# ESCV3.net
KiCad netlist of a schematic drawn in Altium Designer
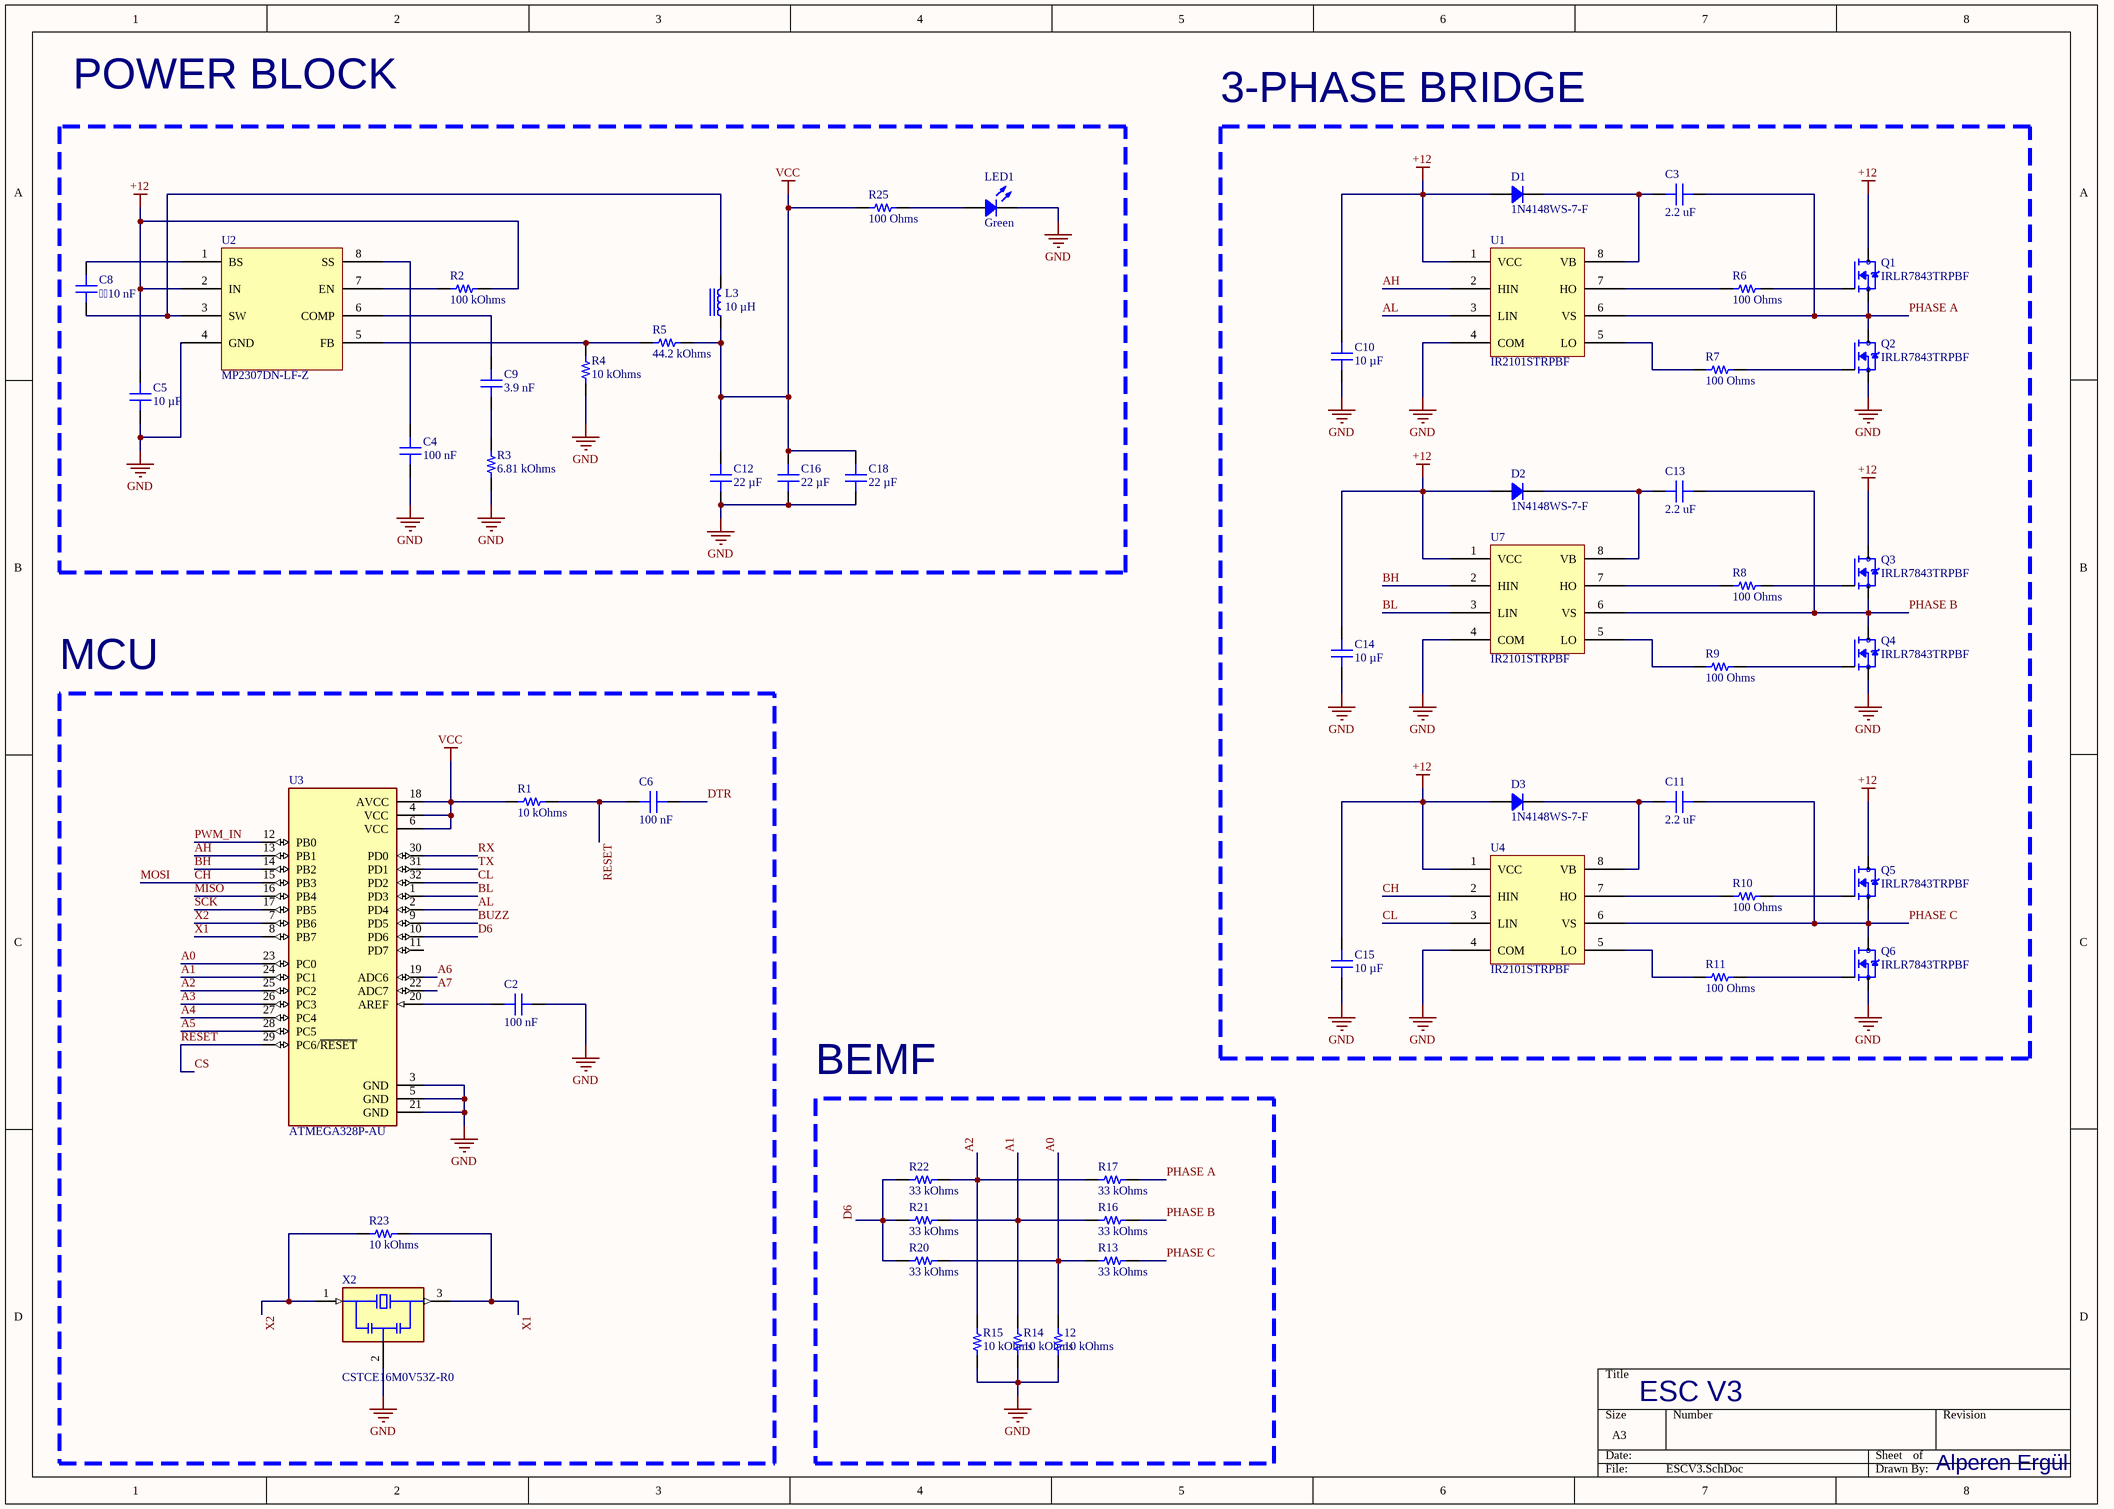
[diagram p0: ESCV3.SchDoc]

(export (version "E")
  (design (tool "Eeschema 10.0.6"))
  (components
    (comp (ref "12")
      (value "10 kOhms")
      (footprint "RES 0603_1608")
      (description "RES 10K OHM 0.1% 1/16W 0603")
      (fields
        (field (name "PART NUMBER") "RNCS0603BKE10K0")
        (field (name "MANUFACTURER") "Stackpole Electronics Inc")
      )
      (libsource (lib "Celestial Altium Library - altium_library") (part "Resistor"))
    )
    (comp (ref "C2")
      (value "100 nF")
      (footprint "CAP 0603_1608")
      (description "CAP CER 3.9PF 250V C0G/NP0 0603")
      (fields (field (name "PART NUMBER") "CBR06C399BAGAC") (field (name "MANUFACTURER") "KEMET"))
      (libsource (lib "Celestial Altium Library - altium_library") (part "Capacitor"))
    )
    (comp (ref "C3")
      (value "2.2 uF")
      (footprint "CAP 0603_1608")
      (description "CAP CER 3.9PF 250V C0G/NP0 0603")
      (fields (field (name "PART NUMBER") "CBR06C399BAGAC") (field (name "MANUFACTURER") "KEMET"))
      (libsource (lib "Celestial Altium Library - altium_library") (part "Capacitor"))
    )
    (comp (ref "C4")
      (value "100 nF")
      (footprint "CAP 0603_1608")
      (description "CAP CER 3.9PF 250V C0G/NP0 0603")
      (fields (field (name "PART NUMBER") "CBR06C399BAGAC") (field (name "MANUFACTURER") "KEMET"))
      (libsource (lib "Celestial Altium Library - altium_library") (part "Capacitor"))
    )
    (comp (ref "C5")
      (value "10 µF")
      (footprint "CAP 1206_3216 - 0.8MM")
      (description "CAP CER 10UF 16V X5R 1206")
      (fields (field (name "PART NUMBER") "EMK316BJ106MD-T") (field (name "MANUFACTURER") "Taiyo Yuden"))
      (libsource (lib "Celestial Altium Library - altium_library") (part "Capacitor"))
    )
    (comp (ref "C6")
      (value "100 nF")
      (footprint "CAP 0603_1608")
      (description "CAP CER 3.9PF 250V C0G/NP0 0603")
      (fields (field (name "PART NUMBER") "CBR06C399BAGAC") (field (name "MANUFACTURER") "KEMET"))
      (libsource (lib "Celestial Altium Library - altium_library") (part "Capacitor"))
    )
    (comp (ref "C8")
      (value "10 nF")
      (footprint "CAP 0603_1608")
      (description "CAP CER 3.9PF 250V C0G/NP0 0603")
      (fields (field (name "PART NUMBER") "CBR06C399BAGAC") (field (name "MANUFACTURER") "KEMET"))
      (libsource (lib "Celestial Altium Library - altium_library") (part "Capacitor"))
    )
    (comp (ref "C9")
      (value "3.9 nF")
      (footprint "CAP 0603_1608")
      (description "CAP CER 3.9PF 250V C0G/NP0 0603")
      (fields (field (name "PART NUMBER") "CBR06C399BAGAC") (field (name "MANUFACTURER") "KEMET"))
      (libsource (lib "Celestial Altium Library - altium_library") (part "Capacitor"))
    )
    (comp (ref "C10")
      (value "10 µF")
      (footprint "CAP 1206_3216 - 0.8MM")
      (description "CAP CER 10UF 16V X5R 1206")
      (fields (field (name "PART NUMBER") "EMK316BJ106MD-T") (field (name "MANUFACTURER") "Taiyo Yuden"))
      (libsource (lib "Celestial Altium Library - altium_library") (part "Capacitor"))
    )
    (comp (ref "C11")
      (value "2.2 uF")
      (footprint "CAP 0603_1608")
      (description "CAP CER 3.9PF 250V C0G/NP0 0603")
      (fields (field (name "PART NUMBER") "CBR06C399BAGAC") (field (name "MANUFACTURER") "KEMET"))
      (libsource (lib "Celestial Altium Library - altium_library") (part "Capacitor"))
    )
    (comp (ref "C12")
      (value "22 µF")
      (footprint "CAP 1206_3216 - 0.8MM")
      (description "CAP CER 22UF 16V X5R 1206")
      (fields
        (field (name "PART NUMBER") "CL31A226MOCLNNC")
        (field (name "MANUFACTURER") "Samsung Electro-Mechanics")
      )
      (libsource (lib "Celestial Altium Library - altium_library") (part "Capacitor"))
    )
    (comp (ref "C13")
      (value "2.2 uF")
      (footprint "CAP 0603_1608")
      (description "CAP CER 3.9PF 250V C0G/NP0 0603")
      (fields (field (name "PART NUMBER") "CBR06C399BAGAC") (field (name "MANUFACTURER") "KEMET"))
      (libsource (lib "Celestial Altium Library - altium_library") (part "Capacitor"))
    )
    (comp (ref "C14")
      (value "10 µF")
      (footprint "CAP 1206_3216 - 0.8MM")
      (description "CAP CER 10UF 16V X5R 1206")
      (fields (field (name "PART NUMBER") "EMK316BJ106MD-T") (field (name "MANUFACTURER") "Taiyo Yuden"))
      (libsource (lib "Celestial Altium Library - altium_library") (part "Capacitor"))
    )
    (comp (ref "C15")
      (value "10 µF")
      (footprint "CAP 1206_3216 - 0.8MM")
      (description "CAP CER 10UF 16V X5R 1206")
      (fields (field (name "PART NUMBER") "EMK316BJ106MD-T") (field (name "MANUFACTURER") "Taiyo Yuden"))
      (libsource (lib "Celestial Altium Library - altium_library") (part "Capacitor"))
    )
    (comp (ref "C16")
      (value "22 µF")
      (footprint "CAP 1206_3216 - 0.8MM")
      (description "CAP CER 22UF 16V X5R 1206")
      (fields
        (field (name "PART NUMBER") "CL31A226MOCLNNC")
        (field (name "MANUFACTURER") "Samsung Electro-Mechanics")
      )
      (libsource (lib "Celestial Altium Library - altium_library") (part "Capacitor"))
    )
    (comp (ref "C18")
      (value "22 µF")
      (footprint "CAP 1206_3216 - 0.8MM")
      (description "CAP CER 22UF 16V X5R 1206")
      (fields
        (field (name "PART NUMBER") "CL31A226MOCLNNC")
        (field (name "MANUFACTURER") "Samsung Electro-Mechanics")
      )
      (libsource (lib "Celestial Altium Library - altium_library") (part "Capacitor"))
    )
    (comp (ref "D1")
      (value "1N4148WS-7-F")
      (footprint "SOD323")
      (description "DIODE GEN PURP 75V 150MA SOD323")
      (fields (field (name "MANUFACTURER") "Diodes Incorporated"))
      (libsource (lib "Celestial Altium Library - altium_library") (part "Diode"))
    )
    (comp (ref "D2")
      (value "1N4148WS-7-F")
      (footprint "SOD323")
      (description "DIODE GEN PURP 75V 150MA SOD323")
      (fields (field (name "MANUFACTURER") "Diodes Incorporated"))
      (libsource (lib "Celestial Altium Library - altium_library") (part "Diode"))
    )
    (comp (ref "D3")
      (value "1N4148WS-7-F")
      (footprint "SOD323")
      (description "DIODE GEN PURP 75V 150MA SOD323")
      (fields (field (name "MANUFACTURER") "Diodes Incorporated"))
      (libsource (lib "Celestial Altium Library - altium_library") (part "Diode"))
    )
    (comp (ref "L3")
      (value "10 µH")
      (footprint "BOURNS SRP5030T")
      (description "FIXED IND 10UH 2.75A 128MOHM SMD")
      (fields (field (name "PART NUMBER") "SRP5030T-100M") (field (name "MANUFACTURER") "Bourns Inc."))
      (libsource (lib "Celestial Altium Library - altium_library") (part "Inductor"))
    )
    (comp (ref "LED1")
      (value "Green")
      (footprint "LED 0603_1608 GREEN")
      (description "LED GREEN CLEAR CHIP 0603 SMD")
      (fields
        (field (name "PART NUMBER") "LSM0603453V")
        (field (name "MANUFACTURER") "Visual Communications Company - VCC")
      )
      (libsource (lib "Celestial Altium Library - altium_library") (part "LED"))
    )
    (comp (ref "Q1")
      (value "IRLR7843TRPBF")
      (footprint "TO229P990X239-3_4N")
      (fields (field (name "MF") "Infineon Technologies"))
      (libsource (lib "IRLR7843TRPBF") (part "IRLR7843TRPBF"))
    )
    (comp (ref "Q2")
      (value "IRLR7843TRPBF")
      (footprint "TO229P990X239-3_4N")
      (fields (field (name "MF") "Infineon Technologies"))
      (libsource (lib "IRLR7843TRPBF") (part "IRLR7843TRPBF"))
    )
    (comp (ref "Q3")
      (value "IRLR7843TRPBF")
      (footprint "TO229P990X239-3_4N")
      (fields (field (name "MF") "Infineon Technologies"))
      (libsource (lib "IRLR7843TRPBF") (part "IRLR7843TRPBF"))
    )
    (comp (ref "Q4")
      (value "IRLR7843TRPBF")
      (footprint "TO229P990X239-3_4N")
      (fields (field (name "MF") "Infineon Technologies"))
      (libsource (lib "IRLR7843TRPBF") (part "IRLR7843TRPBF"))
    )
    (comp (ref "Q5")
      (value "IRLR7843TRPBF")
      (footprint "TO229P990X239-3_4N")
      (fields (field (name "MF") "Infineon Technologies"))
      (libsource (lib "IRLR7843TRPBF") (part "IRLR7843TRPBF"))
    )
    (comp (ref "Q6")
      (value "IRLR7843TRPBF")
      (footprint "TO229P990X239-3_4N")
      (fields (field (name "MF") "Infineon Technologies"))
      (libsource (lib "IRLR7843TRPBF") (part "IRLR7843TRPBF"))
    )
    (comp (ref "R1")
      (value "10 kOhms")
      (footprint "RES 0603_1608")
      (description "RES 10K OHM 0.1% 1/16W 0603")
      (fields
        (field (name "PART NUMBER") "RNCS0603BKE10K0")
        (field (name "MANUFACTURER") "Stackpole Electronics Inc")
      )
      (libsource (lib "Celestial Altium Library - altium_library") (part "Resistor"))
    )
    (comp (ref "R2")
      (value "100 kOhms")
      (footprint "RES 0603_1608")
      (description "RES 100K OHM 0.1% 1/16W 0603")
      (fields
        (field (name "PART NUMBER") "RNCS0603BKE100K")
        (field (name "MANUFACTURER") "Stackpole Electronics Inc")
      )
      (libsource (lib "Celestial Altium Library - altium_library") (part "Resistor"))
    )
    (comp (ref "R3")
      (value "6.81 kOhms")
      (footprint "RES 0603_1608")
      (description "RQ 0603 6K81 0.1% 10PPM 1K RL")
      (fields
        (field (name "PART NUMBER") "RQ73C1J6K81BTDF")
        (field (name "MANUFACTURER") "TE Connectivity Passive Product")
      )
      (libsource (lib "Celestial Altium Library - altium_library") (part "Resistor"))
    )
    (comp (ref "R4")
      (value "10 kOhms")
      (footprint "RES 0603_1608")
      (description "RES 10K OHM 0.1% 1/16W 0603")
      (fields
        (field (name "PART NUMBER") "RNCS0603BKE10K0")
        (field (name "MANUFACTURER") "Stackpole Electronics Inc")
      )
      (libsource (lib "Celestial Altium Library - altium_library") (part "Resistor"))
    )
    (comp (ref "R5")
      (value "44.2 kOhms")
      (footprint "RES 0603_1608")
      (description "RES SMD 44.2K OHM 0.1% 1/5W 0603")
      (fields
        (field (name "PART NUMBER") "ERJ-PB3B4422V")
        (field (name "MANUFACTURER") "Panasonic Electronic Components")
      )
      (libsource (lib "Celestial Altium Library - altium_library") (part "Resistor"))
    )
    (comp (ref "R6")
      (value "100 Ohms")
      (footprint "RES 0603_1608")
      (description "RES 100 OHM 0.1% 1/16W 0603")
      (fields
        (field (name "PART NUMBER") "RNCS0603BKE100R")
        (field (name "MANUFACTURER") "Stackpole Electronics Inc")
      )
      (libsource (lib "Celestial Altium Library - altium_library") (part "Resistor"))
    )
    (comp (ref "R7")
      (value "100 Ohms")
      (footprint "RES 0603_1608")
      (description "RES 100 OHM 0.1% 1/16W 0603")
      (fields
        (field (name "PART NUMBER") "RNCS0603BKE100R")
        (field (name "MANUFACTURER") "Stackpole Electronics Inc")
      )
      (libsource (lib "Celestial Altium Library - altium_library") (part "Resistor"))
    )
    (comp (ref "R8")
      (value "100 Ohms")
      (footprint "RES 0603_1608")
      (description "RES 100 OHM 0.1% 1/16W 0603")
      (fields
        (field (name "PART NUMBER") "RNCS0603BKE100R")
        (field (name "MANUFACTURER") "Stackpole Electronics Inc")
      )
      (libsource (lib "Celestial Altium Library - altium_library") (part "Resistor"))
    )
    (comp (ref "R9")
      (value "100 Ohms")
      (footprint "RES 0603_1608")
      (description "RES 100 OHM 0.1% 1/16W 0603")
      (fields
        (field (name "PART NUMBER") "RNCS0603BKE100R")
        (field (name "MANUFACTURER") "Stackpole Electronics Inc")
      )
      (libsource (lib "Celestial Altium Library - altium_library") (part "Resistor"))
    )
    (comp (ref "R10")
      (value "100 Ohms")
      (footprint "RES 0603_1608")
      (description "RES 100 OHM 0.1% 1/16W 0603")
      (fields
        (field (name "PART NUMBER") "RNCS0603BKE100R")
        (field (name "MANUFACTURER") "Stackpole Electronics Inc")
      )
      (libsource (lib "Celestial Altium Library - altium_library") (part "Resistor"))
    )
    (comp (ref "R11")
      (value "100 Ohms")
      (footprint "RES 0603_1608")
      (description "RES 100 OHM 0.1% 1/16W 0603")
      (fields
        (field (name "PART NUMBER") "RNCS0603BKE100R")
        (field (name "MANUFACTURER") "Stackpole Electronics Inc")
      )
      (libsource (lib "Celestial Altium Library - altium_library") (part "Resistor"))
    )
    (comp (ref "R13")
      (value "33 kOhms")
      (footprint "RES 0603_1608")
      (description "RES SMD 33K OHM 0.1% 1/16W 0603")
      (fields
        (field (name "PART NUMBER") "CPF0603B33KE1")
        (field (name "MANUFACTURER") "TE Connectivity Passive Product")
      )
      (libsource (lib "Celestial Altium Library - altium_library") (part "Resistor"))
    )
    (comp (ref "R14")
      (value "10 kOhms")
      (footprint "RES 0603_1608")
      (description "RES 10K OHM 0.1% 1/16W 0603")
      (fields
        (field (name "PART NUMBER") "RNCS0603BKE10K0")
        (field (name "MANUFACTURER") "Stackpole Electronics Inc")
      )
      (libsource (lib "Celestial Altium Library - altium_library") (part "Resistor"))
    )
    (comp (ref "R15")
      (value "10 kOhms")
      (footprint "RES 0603_1608")
      (description "RES 10K OHM 0.1% 1/16W 0603")
      (fields
        (field (name "PART NUMBER") "RNCS0603BKE10K0")
        (field (name "MANUFACTURER") "Stackpole Electronics Inc")
      )
      (libsource (lib "Celestial Altium Library - altium_library") (part "Resistor"))
    )
    (comp (ref "R16")
      (value "33 kOhms")
      (footprint "RES 0603_1608")
      (description "RES SMD 33K OHM 0.1% 1/16W 0603")
      (fields
        (field (name "PART NUMBER") "CPF0603B33KE1")
        (field (name "MANUFACTURER") "TE Connectivity Passive Product")
      )
      (libsource (lib "Celestial Altium Library - altium_library") (part "Resistor"))
    )
    (comp (ref "R17")
      (value "33 kOhms")
      (footprint "RES 0603_1608")
      (description "RES SMD 33K OHM 0.1% 1/16W 0603")
      (fields
        (field (name "PART NUMBER") "CPF0603B33KE1")
        (field (name "MANUFACTURER") "TE Connectivity Passive Product")
      )
      (libsource (lib "Celestial Altium Library - altium_library") (part "Resistor"))
    )
    (comp (ref "R20")
      (value "33 kOhms")
      (footprint "RES 0603_1608")
      (description "RES SMD 33K OHM 0.1% 1/16W 0603")
      (fields
        (field (name "PART NUMBER") "CPF0603B33KE1")
        (field (name "MANUFACTURER") "TE Connectivity Passive Product")
      )
      (libsource (lib "Celestial Altium Library - altium_library") (part "Resistor"))
    )
    (comp (ref "R21")
      (value "33 kOhms")
      (footprint "RES 0603_1608")
      (description "RES SMD 33K OHM 0.1% 1/16W 0603")
      (fields
        (field (name "PART NUMBER") "CPF0603B33KE1")
        (field (name "MANUFACTURER") "TE Connectivity Passive Product")
      )
      (libsource (lib "Celestial Altium Library - altium_library") (part "Resistor"))
    )
    (comp (ref "R22")
      (value "33 kOhms")
      (footprint "RES 0603_1608")
      (description "RES SMD 33K OHM 0.1% 1/16W 0603")
      (fields
        (field (name "PART NUMBER") "CPF0603B33KE1")
        (field (name "MANUFACTURER") "TE Connectivity Passive Product")
      )
      (libsource (lib "Celestial Altium Library - altium_library") (part "Resistor"))
    )
    (comp (ref "R23")
      (value "10 kOhms")
      (footprint "RES 0603_1608")
      (description "RES 10K OHM 0.1% 1/16W 0603")
      (fields
        (field (name "PART NUMBER") "RNCS0603BKE10K0")
        (field (name "MANUFACTURER") "Stackpole Electronics Inc")
      )
      (libsource (lib "Celestial Altium Library - altium_library") (part "Resistor"))
    )
    (comp (ref "R25")
      (value "100 Ohms")
      (footprint "RES 0603_1608")
      (description "RES 100 OHM 0.1% 1/16W 0603")
      (fields
        (field (name "PART NUMBER") "RNCS0603BKE100R")
        (field (name "MANUFACTURER") "Stackpole Electronics Inc")
      )
      (libsource (lib "Celestial Altium Library - altium_library") (part "Resistor"))
    )
    (comp (ref "U1")
      (value "IR2101STRPBF")
      (footprint "IR2101STRPBF")
      (libsource (lib "ESCV3") (part "IR2101STRPBF"))
    )
    (comp (ref "U2")
      (value "MP2307DN-LF-Z")
      (footprint "MP2307DN-LF-Z")
      (libsource (lib "ESCV3") (part "MP2307DN-LF-Z"))
    )
    (comp (ref "U3")
      (value "ATMEGA328P-AU")
      (footprint "QFP80P900X900X120-32N")
      (description "AVR AVRÂ® ATmega Microcontroller IC 8-Bit 20MHz 32KB (16K x 16) FLASH 32-TQFP (7x7)")
      (fields (field (name "MF") "Microchip Technology"))
      (libsource (lib "ATMEGA328P-AU") (part "ATMEGA328P-AU"))
    )
    (comp (ref "U4")
      (value "IR2101STRPBF")
      (footprint "IR2101STRPBF")
      (libsource (lib "ESCV3") (part "IR2101STRPBF"))
    )
    (comp (ref "U7")
      (value "IR2101STRPBF")
      (footprint "IR2101STRPBF")
      (libsource (lib "ESCV3") (part "IR2101STRPBF"))
    )
    (comp (ref "X2")
      (value "CSTCE16M0V53Z-R0")
      (footprint "OSC_CSTCE16M0V53Z-R0")
      (description "20MHz Ceramic Resonator Built in Capacitor 15pF +/- 0.2% -40C - 125C Surface Mount")
      (fields (field (name "MF") "Murata"))
      (libsource (lib "CSTCE16M0V53Z-R0") (part "CSTCE16M0V53Z-R0"))
    )
  )
  (nets
    (net (code "1") (name "+12") (class "Default")
      (node (ref "C10") (pin "2") (pinfunction "2_2") (pintype "passive"))
      (node (ref "C14") (pin "2") (pinfunction "2_2") (pintype "passive"))
      (node (ref "C15") (pin "2") (pinfunction "2_2") (pintype "passive"))
      (node (ref "C5") (pin "2") (pinfunction "2_2") (pintype "passive"))
      (node (ref "D1") (pin "1") (pinfunction "1_1") (pintype "passive"))
      (node (ref "D2") (pin "1") (pinfunction "1_1") (pintype "passive"))
      (node (ref "D3") (pin "1") (pinfunction "1_1") (pintype "passive"))
      (node (ref "Q1") (pin "4") (pinfunction "D_4") (pintype "passive"))
      (node (ref "Q3") (pin "4") (pinfunction "D_4") (pintype "passive"))
      (node (ref "Q5") (pin "4") (pinfunction "D_4") (pintype "passive"))
      (node (ref "R2") (pin "2") (pinfunction "2_2") (pintype "passive"))
      (node (ref "U1") (pin "1") (pinfunction "VCC_1") (pintype "passive"))
      (node (ref "U2") (pin "2") (pinfunction "IN_2") (pintype "passive"))
      (node (ref "U4") (pin "1") (pinfunction "VCC_1") (pintype "passive"))
      (node (ref "U7") (pin "1") (pinfunction "VCC_1") (pintype "passive"))
    )
    (net (code "2") (name "/A0") (class "Default")
      (node (ref "12") (pin "2") (pinfunction "2_2") (pintype "passive"))
      (node (ref "R13") (pin "1") (pinfunction "1_1") (pintype "passive"))
      (node (ref "R20") (pin "2") (pinfunction "2_2") (pintype "passive"))
      (node (ref "U3") (pin "23") (pinfunction "PC0_23") (pintype "bidirectional"))
    )
    (net (code "3") (name "/A1") (class "Default")
      (node (ref "R14") (pin "2") (pinfunction "2_2") (pintype "passive"))
      (node (ref "R16") (pin "1") (pinfunction "1_1") (pintype "passive"))
      (node (ref "R21") (pin "2") (pinfunction "2_2") (pintype "passive"))
      (node (ref "U3") (pin "24") (pinfunction "PC1_24") (pintype "bidirectional"))
    )
    (net (code "4") (name "/A2") (class "Default")
      (node (ref "R15") (pin "2") (pinfunction "2_2") (pintype "passive"))
      (node (ref "R17") (pin "1") (pinfunction "1_1") (pintype "passive"))
      (node (ref "R22") (pin "2") (pinfunction "2_2") (pintype "passive"))
      (node (ref "U3") (pin "25") (pinfunction "PC2_25") (pintype "bidirectional"))
    )
    (net (code "5") (name "/A3") (class "Default")
      (node (ref "U3") (pin "26") (pinfunction "PC3_26") (pintype "bidirectional"))
    )
    (net (code "6") (name "/A4") (class "Default")
      (node (ref "U3") (pin "27") (pinfunction "PC4_27") (pintype "bidirectional"))
    )
    (net (code "7") (name "/A5") (class "Default")
      (node (ref "U3") (pin "28") (pinfunction "PC5_28") (pintype "bidirectional"))
    )
    (net (code "8") (name "/A6") (class "Default")
      (node (ref "U3") (pin "19") (pinfunction "ADC6_19") (pintype "bidirectional"))
    )
    (net (code "9") (name "/A7") (class "Default")
      (node (ref "U3") (pin "22") (pinfunction "ADC7_22") (pintype "bidirectional"))
    )
    (net (code "10") (name "/AH") (class "Default")
      (node (ref "U1") (pin "2") (pinfunction "HIN_2") (pintype "passive"))
      (node (ref "U3") (pin "13") (pinfunction "PB1_13") (pintype "bidirectional"))
    )
    (net (code "11") (name "/AL") (class "Default")
      (node (ref "U1") (pin "3") (pinfunction "LIN_3") (pintype "passive"))
      (node (ref "U3") (pin "2") (pinfunction "PD4_2") (pintype "bidirectional"))
    )
    (net (code "12") (name "/BH") (class "Default")
      (node (ref "U3") (pin "14") (pinfunction "PB2_14") (pintype "bidirectional"))
      (node (ref "U7") (pin "2") (pinfunction "HIN_2") (pintype "passive"))
    )
    (net (code "13") (name "/BL") (class "Default")
      (node (ref "U3") (pin "1") (pinfunction "PD3_1") (pintype "bidirectional"))
      (node (ref "U7") (pin "3") (pinfunction "LIN_3") (pintype "passive"))
    )
    (net (code "14") (name "/BUZZ") (class "Default")
      (node (ref "U3") (pin "9") (pinfunction "PD5_9") (pintype "bidirectional"))
    )
    (net (code "15") (name "/CH") (class "Default")
      (node (ref "U3") (pin "15") (pinfunction "PB3_15") (pintype "bidirectional"))
      (node (ref "U4") (pin "2") (pinfunction "HIN_2") (pintype "passive"))
    )
    (net (code "16") (name "/CL") (class "Default")
      (node (ref "U3") (pin "32") (pinfunction "PD2_32") (pintype "bidirectional"))
      (node (ref "U4") (pin "3") (pinfunction "LIN_3") (pintype "passive"))
    )
    (net (code "17") (name "/CS") (class "Default")
      (node (ref "C6") (pin "1") (pinfunction "1_1") (pintype "passive"))
      (node (ref "R1") (pin "2") (pinfunction "2_2") (pintype "passive"))
      (node (ref "U3") (pin "29") (pinfunction "PC6/~{RESET}_29") (pintype "bidirectional"))
    )
    (net (code "18") (name "/D6") (class "Default")
      (node (ref "R20") (pin "1") (pinfunction "1_1") (pintype "passive"))
      (node (ref "R21") (pin "1") (pinfunction "1_1") (pintype "passive"))
      (node (ref "R22") (pin "1") (pinfunction "1_1") (pintype "passive"))
      (node (ref "U3") (pin "10") (pinfunction "PD6_10") (pintype "bidirectional"))
    )
    (net (code "19") (name "/DTR") (class "Default")
      (node (ref "C6") (pin "2") (pinfunction "2_2") (pintype "passive"))
    )
    (net (code "20") (name "/MISO") (class "Default")
      (node (ref "U3") (pin "16") (pinfunction "PB4_16") (pintype "bidirectional"))
    )
    (net (code "21") (name "/PHASE A") (class "Default")
      (node (ref "C3") (pin "2") (pinfunction "2_2") (pintype "passive"))
      (node (ref "Q1") (pin "3") (pinfunction "S_3") (pintype "passive"))
      (node (ref "Q2") (pin "4") (pinfunction "D_4") (pintype "passive"))
      (node (ref "R17") (pin "2") (pinfunction "2_2") (pintype "passive"))
      (node (ref "U1") (pin "6") (pinfunction "VS_6") (pintype "passive"))
    )
    (net (code "22") (name "/PHASE B") (class "Default")
      (node (ref "C13") (pin "2") (pinfunction "2_2") (pintype "passive"))
      (node (ref "Q3") (pin "3") (pinfunction "S_3") (pintype "passive"))
      (node (ref "Q4") (pin "4") (pinfunction "D_4") (pintype "passive"))
      (node (ref "R16") (pin "2") (pinfunction "2_2") (pintype "passive"))
      (node (ref "U7") (pin "6") (pinfunction "VS_6") (pintype "passive"))
    )
    (net (code "23") (name "/PHASE C") (class "Default")
      (node (ref "C11") (pin "2") (pinfunction "2_2") (pintype "passive"))
      (node (ref "Q5") (pin "3") (pinfunction "S_3") (pintype "passive"))
      (node (ref "Q6") (pin "4") (pinfunction "D_4") (pintype "passive"))
      (node (ref "R13") (pin "2") (pinfunction "2_2") (pintype "passive"))
      (node (ref "U4") (pin "6") (pinfunction "VS_6") (pintype "passive"))
    )
    (net (code "24") (name "/PWM_IN") (class "Default")
      (node (ref "U3") (pin "12") (pinfunction "PB0_12") (pintype "bidirectional"))
    )
    (net (code "25") (name "/RX") (class "Default")
      (node (ref "U3") (pin "30") (pinfunction "PD0_30") (pintype "bidirectional"))
    )
    (net (code "26") (name "/SCK") (class "Default")
      (node (ref "U3") (pin "17") (pinfunction "PB5_17") (pintype "bidirectional"))
    )
    (net (code "27") (name "/TX") (class "Default")
      (node (ref "U3") (pin "31") (pinfunction "PD1_31") (pintype "bidirectional"))
    )
    (net (code "28") (name "/X1") (class "Default")
      (node (ref "R23") (pin "2") (pinfunction "2_2") (pintype "passive"))
      (node (ref "U3") (pin "8") (pinfunction "PB7_8") (pintype "bidirectional"))
      (node (ref "X2") (pin "3") (pinfunction "OUT_3") (pintype "output"))
    )
    (net (code "29") (name "/X2") (class "Default")
      (node (ref "R23") (pin "1") (pinfunction "1_1") (pintype "passive"))
      (node (ref "U3") (pin "7") (pinfunction "PB6_7") (pintype "bidirectional"))
      (node (ref "X2") (pin "1") (pinfunction "IN_1") (pintype "input"))
    )
    (net (code "30") (name "GND") (class "Default")
      (node (ref "12") (pin "1") (pinfunction "1_1") (pintype "passive"))
      (node (ref "C10") (pin "1") (pinfunction "1_1") (pintype "passive"))
      (node (ref "C12") (pin "1") (pinfunction "1_1") (pintype "passive"))
      (node (ref "C14") (pin "1") (pinfunction "1_1") (pintype "passive"))
      (node (ref "C15") (pin "1") (pinfunction "1_1") (pintype "passive"))
      (node (ref "C16") (pin "1") (pinfunction "1_1") (pintype "passive"))
      (node (ref "C18") (pin "1") (pinfunction "1_1") (pintype "passive"))
      (node (ref "C2") (pin "2") (pinfunction "2_2") (pintype "passive"))
      (node (ref "C4") (pin "1") (pinfunction "1_1") (pintype "passive"))
      (node (ref "C5") (pin "1") (pinfunction "1_1") (pintype "passive"))
      (node (ref "LED1") (pin "2") (pinfunction "2_2") (pintype "passive"))
      (node (ref "Q2") (pin "3") (pinfunction "S_3") (pintype "passive"))
      (node (ref "Q4") (pin "3") (pinfunction "S_3") (pintype "passive"))
      (node (ref "Q6") (pin "3") (pinfunction "S_3") (pintype "passive"))
      (node (ref "R14") (pin "1") (pinfunction "1_1") (pintype "passive"))
      (node (ref "R15") (pin "1") (pinfunction "1_1") (pintype "passive"))
      (node (ref "R3") (pin "1") (pinfunction "1_1") (pintype "passive"))
      (node (ref "R4") (pin "1") (pinfunction "1_1") (pintype "passive"))
      (node (ref "U1") (pin "4") (pinfunction "COM_4") (pintype "passive"))
      (node (ref "U2") (pin "4") (pinfunction "GND_4") (pintype "passive"))
      (node (ref "U3") (pin "21") (pinfunction "GND_21") (pintype "power_in"))
      (node (ref "U3") (pin "3") (pinfunction "GND_3") (pintype "power_in"))
      (node (ref "U3") (pin "5") (pinfunction "GND_5") (pintype "power_in"))
      (node (ref "U4") (pin "4") (pinfunction "COM_4") (pintype "passive"))
      (node (ref "U7") (pin "4") (pinfunction "COM_4") (pintype "passive"))
      (node (ref "X2") (pin "2") (pinfunction "GND_2") (pintype "power_in"))
    )
    (net (code "31") (name "Net-(C9-Pad1)") (class "Default")
      (node (ref "C9") (pin "1") (pinfunction "1_1") (pintype "passive"))
      (node (ref "R3") (pin "2") (pinfunction "2_2") (pintype "passive"))
    )
    (net (code "32") (name "Net-(LED1-Pad1)") (class "Default")
      (node (ref "LED1") (pin "1") (pinfunction "1_1") (pintype "passive"))
      (node (ref "R25") (pin "2") (pinfunction "2_2") (pintype "passive"))
    )
    (net (code "33") (name "Net-(Q1-G)") (class "Default")
      (node (ref "Q1") (pin "1") (pinfunction "G_1") (pintype "passive"))
      (node (ref "R6") (pin "2") (pinfunction "2_2") (pintype "passive"))
    )
    (net (code "34") (name "Net-(Q2-G)") (class "Default")
      (node (ref "Q2") (pin "1") (pinfunction "G_1") (pintype "passive"))
      (node (ref "R7") (pin "2") (pinfunction "2_2") (pintype "passive"))
    )
    (net (code "35") (name "Net-(Q3-G)") (class "Default")
      (node (ref "Q3") (pin "1") (pinfunction "G_1") (pintype "passive"))
      (node (ref "R8") (pin "2") (pinfunction "2_2") (pintype "passive"))
    )
    (net (code "36") (name "Net-(Q4-G)") (class "Default")
      (node (ref "Q4") (pin "1") (pinfunction "G_1") (pintype "passive"))
      (node (ref "R9") (pin "2") (pinfunction "2_2") (pintype "passive"))
    )
    (net (code "37") (name "Net-(Q5-G)") (class "Default")
      (node (ref "Q5") (pin "1") (pinfunction "G_1") (pintype "passive"))
      (node (ref "R10") (pin "2") (pinfunction "2_2") (pintype "passive"))
    )
    (net (code "38") (name "Net-(Q6-G)") (class "Default")
      (node (ref "Q6") (pin "1") (pinfunction "G_1") (pintype "passive"))
      (node (ref "R11") (pin "2") (pinfunction "2_2") (pintype "passive"))
    )
    (net (code "39") (name "Net-(U1-HO)") (class "Default")
      (node (ref "R6") (pin "1") (pinfunction "1_1") (pintype "passive"))
      (node (ref "U1") (pin "7") (pinfunction "HO_7") (pintype "passive"))
    )
    (net (code "40") (name "Net-(U1-LO)") (class "Default")
      (node (ref "R7") (pin "1") (pinfunction "1_1") (pintype "passive"))
      (node (ref "U1") (pin "5") (pinfunction "LO_5") (pintype "passive"))
    )
    (net (code "41") (name "Net-(U1-VB)") (class "Default")
      (node (ref "C3") (pin "1") (pinfunction "1_1") (pintype "passive"))
      (node (ref "D1") (pin "2") (pinfunction "2_2") (pintype "passive"))
      (node (ref "U1") (pin "8") (pinfunction "VB_8") (pintype "passive"))
    )
    (net (code "42") (name "Net-(U2-BS)") (class "Default")
      (node (ref "C8") (pin "1") (pinfunction "1_1") (pintype "passive"))
      (node (ref "U2") (pin "1") (pinfunction "BS_1") (pintype "passive"))
    )
    (net (code "43") (name "Net-(U2-COMP)") (class "Default")
      (node (ref "C9") (pin "2") (pinfunction "2_2") (pintype "passive"))
      (node (ref "U2") (pin "6") (pinfunction "COMP_6") (pintype "passive"))
    )
    (net (code "44") (name "Net-(U2-EN)") (class "Default")
      (node (ref "R2") (pin "1") (pinfunction "1_1") (pintype "passive"))
      (node (ref "U2") (pin "7") (pinfunction "EN_7") (pintype "passive"))
    )
    (net (code "45") (name "Net-(U2-FB)") (class "Default")
      (node (ref "R4") (pin "2") (pinfunction "2_2") (pintype "passive"))
      (node (ref "R5") (pin "1") (pinfunction "1_1") (pintype "passive"))
      (node (ref "U2") (pin "5") (pinfunction "FB_5") (pintype "passive"))
    )
    (net (code "46") (name "Net-(U2-SS)") (class "Default")
      (node (ref "C4") (pin "2") (pinfunction "2_2") (pintype "passive"))
      (node (ref "U2") (pin "8") (pinfunction "SS_8") (pintype "passive"))
    )
    (net (code "47") (name "Net-(U2-SW)") (class "Default")
      (node (ref "C8") (pin "2") (pinfunction "2_2") (pintype "passive"))
      (node (ref "L3") (pin "2") (pinfunction "2_2") (pintype "passive"))
      (node (ref "U2") (pin "3") (pinfunction "SW_3") (pintype "passive"))
    )
    (net (code "48") (name "Net-(U3-AREF)") (class "Default")
      (node (ref "C2") (pin "1") (pinfunction "1_1") (pintype "passive"))
      (node (ref "U3") (pin "20") (pinfunction "AREF_20") (pintype "input"))
    )
    (net (code "49") (name "Net-(U4-HO)") (class "Default")
      (node (ref "R10") (pin "1") (pinfunction "1_1") (pintype "passive"))
      (node (ref "U4") (pin "7") (pinfunction "HO_7") (pintype "passive"))
    )
    (net (code "50") (name "Net-(U4-LO)") (class "Default")
      (node (ref "R11") (pin "1") (pinfunction "1_1") (pintype "passive"))
      (node (ref "U4") (pin "5") (pinfunction "LO_5") (pintype "passive"))
    )
    (net (code "51") (name "Net-(U4-VB)") (class "Default")
      (node (ref "C11") (pin "1") (pinfunction "1_1") (pintype "passive"))
      (node (ref "D3") (pin "2") (pinfunction "2_2") (pintype "passive"))
      (node (ref "U4") (pin "8") (pinfunction "VB_8") (pintype "passive"))
    )
    (net (code "52") (name "Net-(U7-HO)") (class "Default")
      (node (ref "R8") (pin "1") (pinfunction "1_1") (pintype "passive"))
      (node (ref "U7") (pin "7") (pinfunction "HO_7") (pintype "passive"))
    )
    (net (code "53") (name "Net-(U7-LO)") (class "Default")
      (node (ref "R9") (pin "1") (pinfunction "1_1") (pintype "passive"))
      (node (ref "U7") (pin "5") (pinfunction "LO_5") (pintype "passive"))
    )
    (net (code "54") (name "Net-(U7-VB)") (class "Default")
      (node (ref "C13") (pin "1") (pinfunction "1_1") (pintype "passive"))
      (node (ref "D2") (pin "2") (pinfunction "2_2") (pintype "passive"))
      (node (ref "U7") (pin "8") (pinfunction "VB_8") (pintype "passive"))
    )
    (net (code "55") (name "VCC") (class "Default")
      (node (ref "C12") (pin "2") (pinfunction "2_2") (pintype "passive"))
      (node (ref "C16") (pin "2") (pinfunction "2_2") (pintype "passive"))
      (node (ref "C18") (pin "2") (pinfunction "2_2") (pintype "passive"))
      (node (ref "L3") (pin "1") (pinfunction "1_1") (pintype "passive"))
      (node (ref "R1") (pin "1") (pinfunction "1_1") (pintype "passive"))
      (node (ref "R25") (pin "1") (pinfunction "1_1") (pintype "passive"))
      (node (ref "R5") (pin "2") (pinfunction "2_2") (pintype "passive"))
      (node (ref "U3") (pin "18") (pinfunction "AVCC_18") (pintype "power_in"))
      (node (ref "U3") (pin "4") (pinfunction "VCC_4") (pintype "power_in"))
      (node (ref "U3") (pin "6") (pinfunction "VCC_6") (pintype "power_in"))
    )
    (net (code "56") (name "unconnected-(U3-PD7-Pad11)") (class "Default")
      (node (ref "U3") (pin "11") (pinfunction "PD7_11") (pintype "bidirectional"))
    )
  )
)
